# 4_downstream_power.net
KiCad netlist of a schematic drawn in Altium Designer
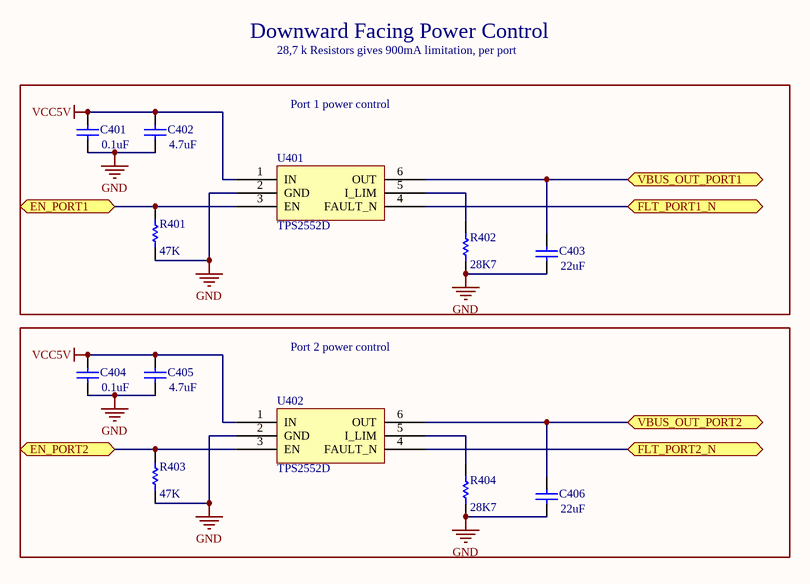
[diagram p0: 4_downstream_power.SchDoc]

(export (version "E")
  (design (tool "Eeschema 10.0.6"))
  (components
    (comp (ref "C401")
      (value "0.1uF")
      (footprint "C0603[1608]")
      (description "Capacitor")
      (fields (field (name "MFG") "KEMET"))
      (libsource (lib "Miscellaneous Devices") (part "Cap"))
    )
    (comp (ref "C402")
      (value "4.7uF")
      (footprint "C1206[3216]")
      (description "Capacitor")
      (fields (field (name "MFG") "KEMET"))
      (libsource (lib "Miscellaneous Devices") (part "Cap"))
    )
    (comp (ref "C403")
      (value "22uF")
      (footprint "C1206[3216]")
      (description "Capacitor")
      (fields (field (name "MFG") "KEMET"))
      (libsource (lib "Miscellaneous Devices") (part "Cap"))
    )
    (comp (ref "C404")
      (value "0.1uF")
      (footprint "C0603[1608]")
      (description "Capacitor")
      (fields (field (name "MFG") "KEMET"))
      (libsource (lib "Miscellaneous Devices") (part "Cap"))
    )
    (comp (ref "C405")
      (value "4.7uF")
      (footprint "C1206[3216]")
      (description "Capacitor")
      (fields (field (name "MFG") "KEMET"))
      (libsource (lib "Miscellaneous Devices") (part "Cap"))
    )
    (comp (ref "C406")
      (value "22uF")
      (footprint "C1206[3216]")
      (description "Capacitor")
      (fields (field (name "MFG") "KEMET"))
      (libsource (lib "Miscellaneous Devices") (part "Cap"))
    )
    (comp (ref "R401")
      (value "47K")
      (footprint "R0603[1608]")
      (description "Resistor")
      (fields (field (name "MFG") "Vishay Dale"))
      (libsource (lib "Miscellaneous Devices") (part "Res1"))
    )
    (comp (ref "R402")
      (value "28K7")
      (footprint "R0603[1608]")
      (description "Resistor")
      (fields (field (name "MFG") "Vishay Dale"))
      (libsource (lib "Miscellaneous Devices") (part "Res1"))
    )
    (comp (ref "R403")
      (value "47K")
      (footprint "R0603[1608]")
      (description "Resistor")
      (fields (field (name "MFG") "Vishay Dale"))
      (libsource (lib "Miscellaneous Devices") (part "Res1"))
    )
    (comp (ref "R404")
      (value "28K7")
      (footprint "R0603[1608]")
      (description "Resistor")
      (fields (field (name "MFG") "Vishay Dale"))
      (libsource (lib "Miscellaneous Devices") (part "Res1"))
    )
    (comp (ref "U401")
      (value "TPS2552D")
      (footprint "SOT-23-6")
      (fields (field (name "MFG") "Texas Instruments"))
      (libsource (lib "lib") (part "TPS2552D"))
    )
    (comp (ref "U402")
      (value "TPS2552D")
      (footprint "SOT-23-6")
      (fields (field (name "MFG") "Texas Instruments"))
      (libsource (lib "lib") (part "TPS2552D"))
    )
  )
  (nets
    (net (code "1") (name "/EN_PORT1") (class "Default")
      (node (ref "R401") (pin "1") (pinfunction "1_1") (pintype "passive"))
      (node (ref "U401") (pin "3") (pinfunction "EN_3") (pintype "passive"))
    )
    (net (code "2") (name "/EN_PORT2") (class "Default")
      (node (ref "R403") (pin "1") (pinfunction "1_1") (pintype "passive"))
      (node (ref "U402") (pin "3") (pinfunction "EN_3") (pintype "passive"))
    )
    (net (code "3") (name "/FLT_PORT1_N") (class "Default")
      (node (ref "U401") (pin "4") (pinfunction "FAULT_N_4") (pintype "passive"))
    )
    (net (code "4") (name "/FLT_PORT2_N") (class "Default")
      (node (ref "U402") (pin "4") (pinfunction "FAULT_N_4") (pintype "passive"))
    )
    (net (code "5") (name "/VBUS_OUT_PORT1") (class "Default")
      (node (ref "C403") (pin "2") (pinfunction "2_2") (pintype "passive"))
      (node (ref "U401") (pin "6") (pinfunction "OUT_6") (pintype "passive"))
    )
    (net (code "6") (name "/VBUS_OUT_PORT2") (class "Default")
      (node (ref "C406") (pin "2") (pinfunction "2_2") (pintype "passive"))
      (node (ref "U402") (pin "6") (pinfunction "OUT_6") (pintype "passive"))
    )
    (net (code "7") (name "GND") (class "Default")
      (node (ref "C401") (pin "1") (pinfunction "1_1") (pintype "passive"))
      (node (ref "C402") (pin "1") (pinfunction "1_1") (pintype "passive"))
      (node (ref "C403") (pin "1") (pinfunction "1_1") (pintype "passive"))
      (node (ref "C404") (pin "1") (pinfunction "1_1") (pintype "passive"))
      (node (ref "C405") (pin "1") (pinfunction "1_1") (pintype "passive"))
      (node (ref "C406") (pin "1") (pinfunction "1_1") (pintype "passive"))
      (node (ref "R401") (pin "2") (pinfunction "2_2") (pintype "passive"))
      (node (ref "R402") (pin "2") (pinfunction "2_2") (pintype "passive"))
      (node (ref "R403") (pin "2") (pinfunction "2_2") (pintype "passive"))
      (node (ref "R404") (pin "2") (pinfunction "2_2") (pintype "passive"))
      (node (ref "U401") (pin "2") (pinfunction "GND_2") (pintype "passive"))
      (node (ref "U402") (pin "2") (pinfunction "GND_2") (pintype "passive"))
    )
    (net (code "8") (name "Net-(U401-I_LIM)") (class "Default")
      (node (ref "R402") (pin "1") (pinfunction "1_1") (pintype "passive"))
      (node (ref "U401") (pin "5") (pinfunction "I_LIM_5") (pintype "passive"))
    )
    (net (code "9") (name "Net-(U402-I_LIM)") (class "Default")
      (node (ref "R404") (pin "1") (pinfunction "1_1") (pintype "passive"))
      (node (ref "U402") (pin "5") (pinfunction "I_LIM_5") (pintype "passive"))
    )
    (net (code "10") (name "VCC5V") (class "Default")
      (node (ref "C401") (pin "2") (pinfunction "2_2") (pintype "passive"))
      (node (ref "C402") (pin "2") (pinfunction "2_2") (pintype "passive"))
      (node (ref "C404") (pin "2") (pinfunction "2_2") (pintype "passive"))
      (node (ref "C405") (pin "2") (pinfunction "2_2") (pintype "passive"))
      (node (ref "U401") (pin "1") (pinfunction "IN_1") (pintype "passive"))
      (node (ref "U402") (pin "1") (pinfunction "IN_1") (pintype "passive"))
    )
  )
)
